# bob-power-board.net
KiCad netlist of a schematic drawn in EAGLE
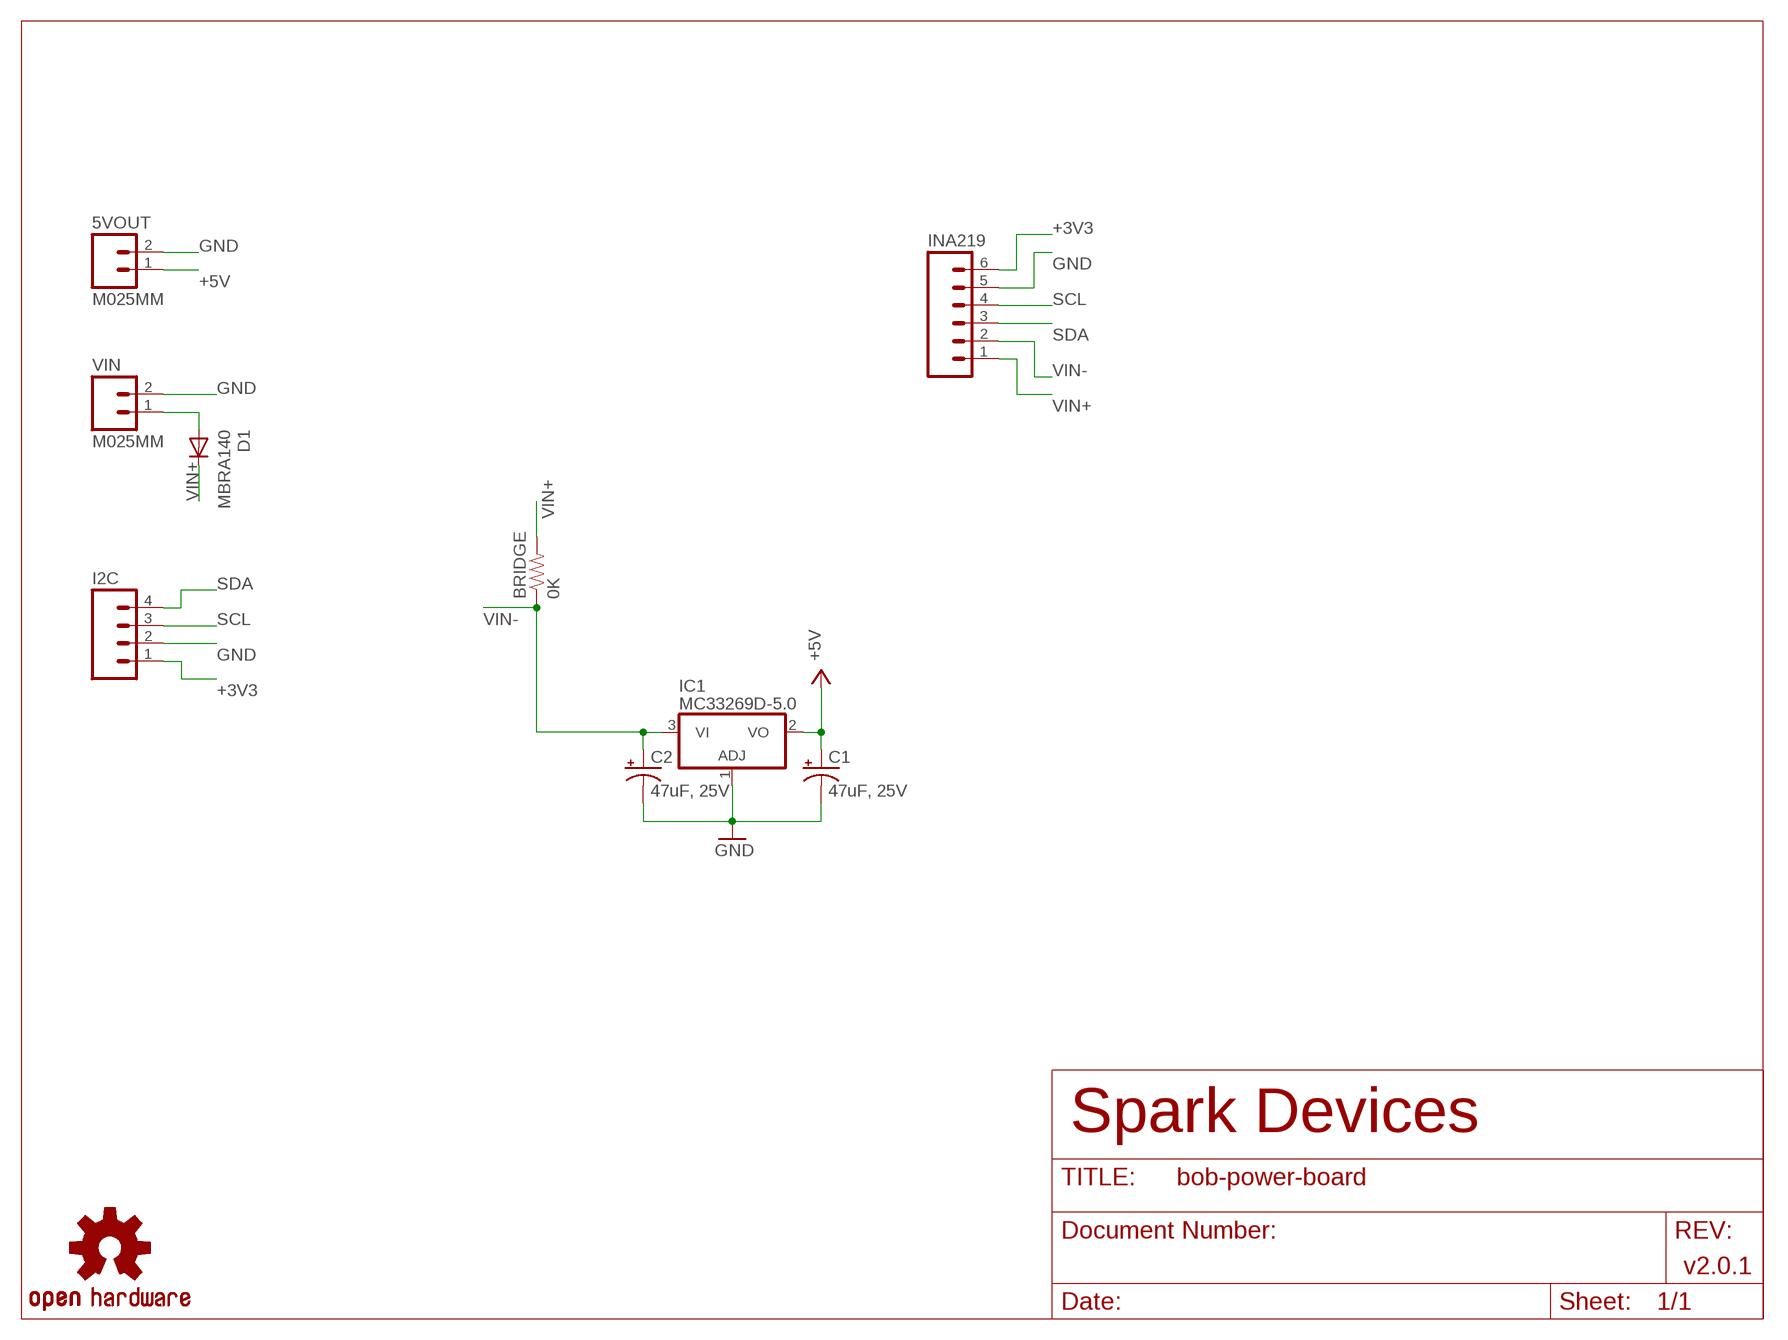
[diagram p0: schematic, sheet 1]

(export (version "E")
  (design (tool "Eeschema 10.0.6"))
  (components
    (comp (ref "5VOUT")
      (value "M025MM")
      (footprint "eagle-import:SCREWTERMINAL-5MM-2")
      (libsource (lib "eagle-import") (part "M025MM"))
    )
    (comp (ref "BRIDGE")
      (value "0K")
      (footprint "eagle-import:1206")
      (libsource (lib "eagle-import") (part "RESISTOR1206"))
    )
    (comp (ref "C1")
      (value "47uF, 25V")
      (footprint "eagle-import:CPOL-RADIAL-100UF-25V")
      (libsource (lib "eagle-import") (part "CAP_POLPTH1"))
    )
    (comp (ref "C2")
      (value "47uF, 25V")
      (footprint "eagle-import:CPOL-RADIAL-100UF-25V")
      (libsource (lib "eagle-import") (part "CAP_POLPTH1"))
    )
    (comp (ref "D1")
      (value "MBRA140")
      (footprint "eagle-import:SMA-DIODE")
      (libsource (lib "eagle-import") (part "DIODESMA"))
    )
    (comp (ref "I2C")
      (value "M04LOCK")
      (footprint "eagle-import:1X04_LOCK")
      (libsource (lib "eagle-import") (part "M04LOCK"))
    )
    (comp (ref "IC1")
      (value "MC33269D-5.0")
      (footprint "eagle-import:DPACK")
      (libsource (lib "eagle-import") (part "MC33269?D-5.0"))
    )
    (comp (ref "INA219")
      (value "M06LOCK")
      (footprint "eagle-import:1X06_LOCK")
      (libsource (lib "eagle-import") (part "M06LOCK"))
    )
    (comp (ref "LOGO1")
      (value "OSHW-LOGOM")
      (footprint "eagle-import:OSHW-LOGO-M")
      (libsource (lib "eagle-import") (part "OSHW-LOGOM"))
    )
    (comp (ref "VIN")
      (value "M025MM")
      (footprint "eagle-import:SCREWTERMINAL-5MM-2")
      (libsource (lib "eagle-import") (part "M025MM"))
    )
  )
  (nets
    (net (code "1") (name "+5V") (class "Default")
      (node (ref "5VOUT") (pin "1") (pinfunction "1_1") (pintype "passive"))
      (node (ref "C1") (pin "1") (pinfunction "+_1") (pintype "passive"))
      (node (ref "IC1") (pin "2") (pinfunction "VO_2") (pintype "passive"))
    )
    (net (code "2") (name "/+3V3") (class "Default")
      (node (ref "I2C") (pin "1") (pinfunction "1_1") (pintype "passive"))
      (node (ref "INA219") (pin "6") (pinfunction "6_6") (pintype "passive"))
    )
    (net (code "3") (name "/SCL") (class "Default")
      (node (ref "I2C") (pin "3") (pinfunction "3_3") (pintype "passive"))
      (node (ref "INA219") (pin "4") (pinfunction "4_4") (pintype "passive"))
    )
    (net (code "4") (name "/SDA") (class "Default")
      (node (ref "I2C") (pin "4") (pinfunction "4_4") (pintype "passive"))
      (node (ref "INA219") (pin "3") (pinfunction "3_3") (pintype "passive"))
    )
    (net (code "5") (name "/VIN+") (class "Default")
      (node (ref "BRIDGE") (pin "2") (pinfunction "2_2") (pintype "passive"))
      (node (ref "D1") (pin "C") (pinfunction "C_C") (pintype "passive"))
      (node (ref "INA219") (pin "1") (pinfunction "1_1") (pintype "passive"))
    )
    (net (code "6") (name "/VIN-") (class "Default")
      (node (ref "BRIDGE") (pin "1") (pinfunction "1_1") (pintype "passive"))
      (node (ref "C2") (pin "1") (pinfunction "+_1") (pintype "passive"))
      (node (ref "IC1") (pin "3") (pinfunction "VI_3") (pintype "input"))
      (node (ref "INA219") (pin "2") (pinfunction "2_2") (pintype "passive"))
    )
    (net (code "7") (name "GND") (class "Default")
      (node (ref "5VOUT") (pin "2") (pinfunction "2_2") (pintype "passive"))
      (node (ref "C1") (pin "2") (pinfunction "-_2") (pintype "passive"))
      (node (ref "C2") (pin "2") (pinfunction "-_2") (pintype "passive"))
      (node (ref "I2C") (pin "2") (pinfunction "2_2") (pintype "passive"))
      (node (ref "IC1") (pin "1") (pinfunction "ADJ_1") (pintype "input"))
      (node (ref "INA219") (pin "5") (pinfunction "5_5") (pintype "passive"))
      (node (ref "VIN") (pin "2") (pinfunction "2_2") (pintype "passive"))
    )
    (net (code "8") (name "Net-(D1-PadA)") (class "Default")
      (node (ref "D1") (pin "A") (pinfunction "A_A") (pintype "passive"))
      (node (ref "VIN") (pin "1") (pinfunction "1_1") (pintype "passive"))
    )
  )
)
